# CON_PS2_MINIDIN6F.net
KiCad netlist of a schematic drawn in Altium Designer
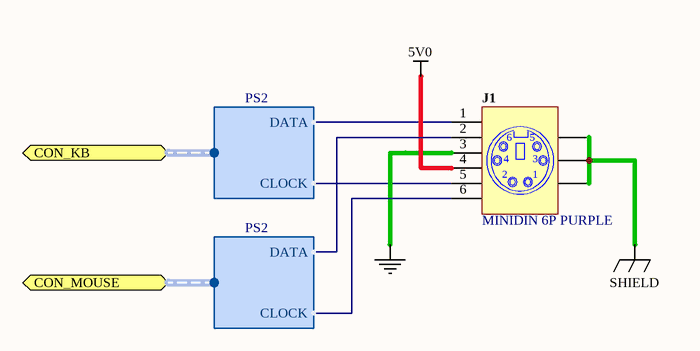
[diagram p0: CON_PS2_MINIDIN6F.SchDoc]

(export (version "E")
  (design (tool "Eeschema 10.0.6"))
  (components
    (comp (ref "J1")
      (value "MINIDIN 6P PURPLE")
      (footprint "MINIDIN6PURPLE")
      (description "MINI DIN R/A F/SHLD 6P GOLD PLATED--PURPLE PC99 RoHS Compliant")
      (libsource (lib "AltiumDesignLibrary") (part "CON-MINIDIN-6-F"))
    )
  )
  (nets
    (net (code "3") (name "5V0") (class "Default")
      (node (ref "J1") (pin "4") (pinfunction "4_4") (pintype "passive"))
    )
    (net (code "4") (name "GND") (class "Default")
      (node (ref "J1") (pin "3") (pinfunction "3_3") (pintype "passive"))
    )
    (net (code "5") (name "SHIELD") (class "Default")
      (node (ref "J1") (pin "MH1") (pinfunction "MH1_MH1") (pintype "passive"))
      (node (ref "J1") (pin "MH2") (pinfunction "MH2_MH2") (pintype "passive"))
      (node (ref "J1") (pin "MH3") (pinfunction "MH3_MH3") (pintype "passive"))
    )
    (net (code "6") (name "unconnected-(J1-Pad1)") (class "Default")
      (node (ref "J1") (pin "1") (pinfunction "1_1") (pintype "passive"))
    )
    (net (code "7") (name "unconnected-(J1-Pad2)") (class "Default")
      (node (ref "J1") (pin "2") (pinfunction "2_2") (pintype "passive"))
    )
    (net (code "8") (name "unconnected-(J1-Pad5)") (class "Default")
      (node (ref "J1") (pin "5") (pinfunction "5_5") (pintype "passive"))
    )
    (net (code "9") (name "unconnected-(J1-Pad6)") (class "Default")
      (node (ref "J1") (pin "6") (pinfunction "6_6") (pintype "passive"))
    )
  )
)
